# V2.net
KiCad netlist of a schematic drawn in EasyEDA
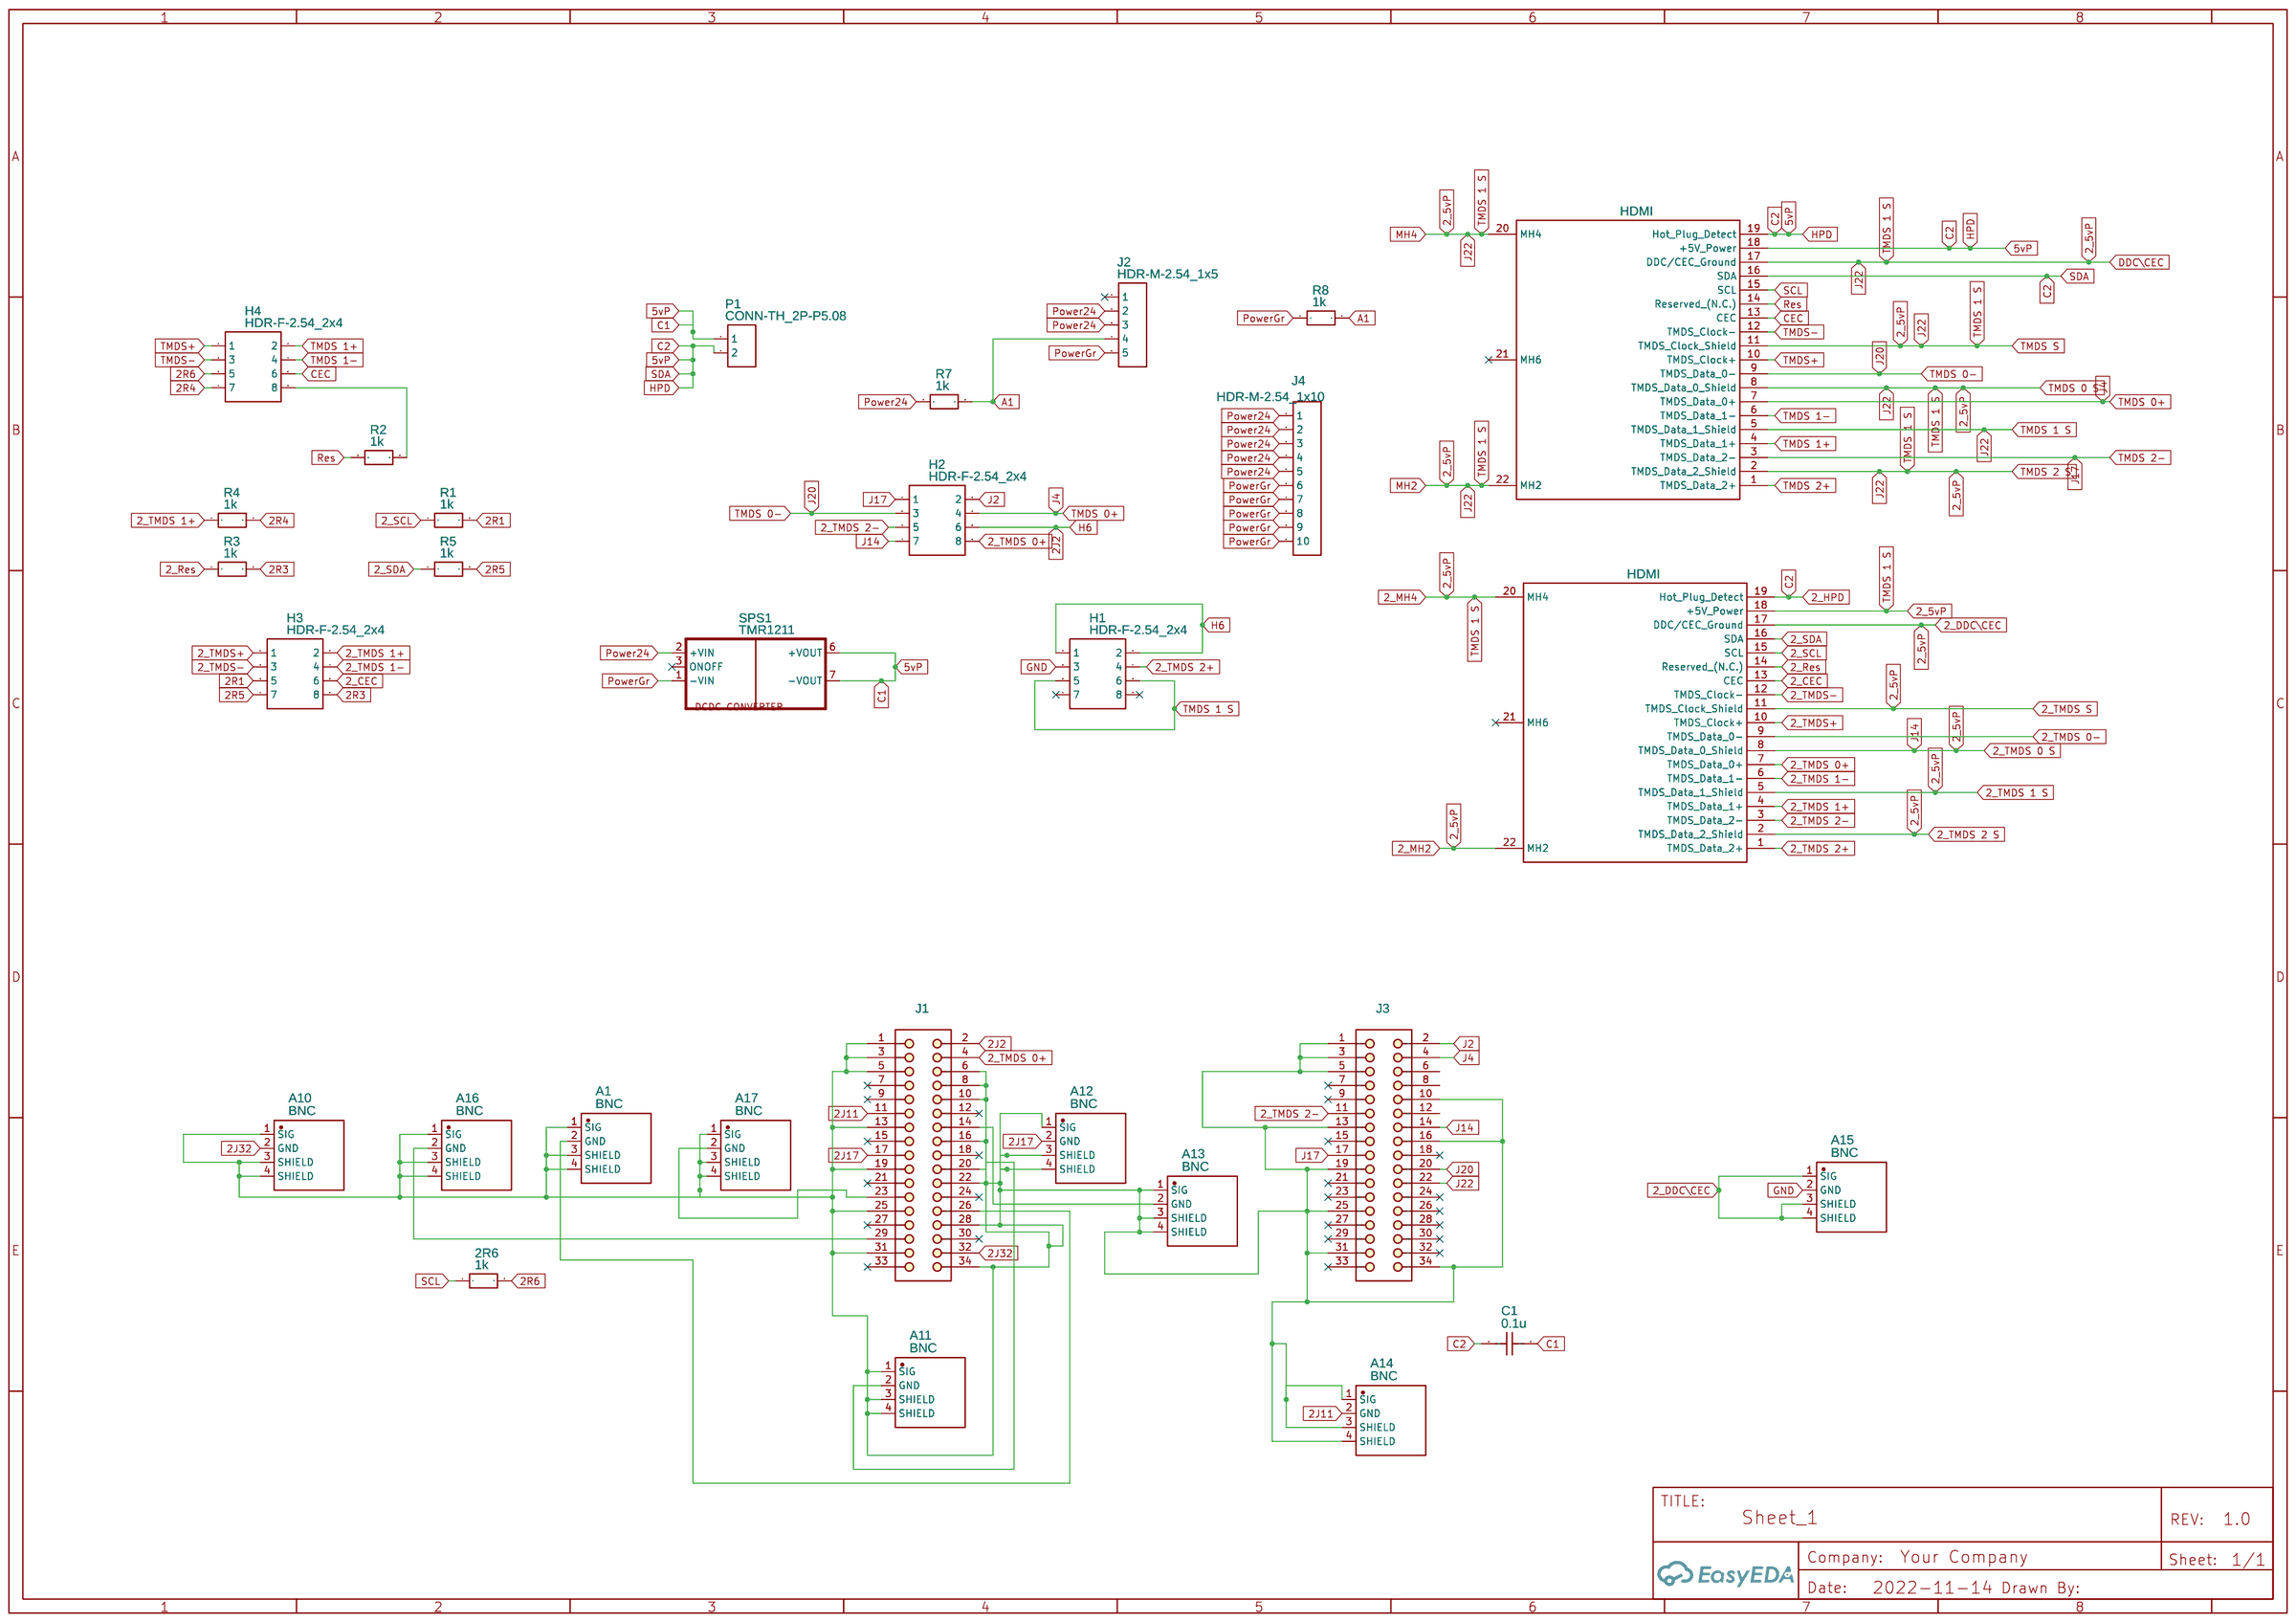
[diagram p0: schematic sheet]

(export (version "E")
  (design (tool "Eeschema 10.0.6"))
  (components
    (comp (ref "2R6") (value "1k") (libsource (lib "") (part "R_0603_EU_1")))
    (comp (ref "A1")
      (value "BNC")
      (fields
        (field (name "BOM_Manufacturer Part") "DOSIN-801-0039")
        (field (name "BOM_Supplier Part") "C709674")
      )
      (libsource (lib "") (part "DOSIN-801-0039"))
    )
    (comp (ref "A10")
      (value "BNC")
      (fields
        (field (name "BOM_Manufacturer Part") "DOSIN-801-0039")
        (field (name "BOM_Supplier Part") "C709674")
      )
      (libsource (lib "") (part "DOSIN-801-0039"))
    )
    (comp (ref "A11")
      (value "BNC")
      (fields
        (field (name "BOM_Manufacturer Part") "DOSIN-801-0039")
        (field (name "BOM_Supplier Part") "C709674")
      )
      (libsource (lib "") (part "DOSIN-801-0039"))
    )
    (comp (ref "A12")
      (value "BNC")
      (fields
        (field (name "BOM_Manufacturer Part") "DOSIN-801-0039")
        (field (name "BOM_Supplier Part") "C709674")
      )
      (libsource (lib "") (part "DOSIN-801-0039"))
    )
    (comp (ref "A13")
      (value "BNC")
      (fields
        (field (name "BOM_Manufacturer Part") "DOSIN-801-0039")
        (field (name "BOM_Supplier Part") "C709674")
      )
      (libsource (lib "") (part "DOSIN-801-0039"))
    )
    (comp (ref "A14")
      (value "BNC")
      (fields
        (field (name "BOM_Manufacturer Part") "DOSIN-801-0039")
        (field (name "BOM_Supplier Part") "C709674")
      )
      (libsource (lib "") (part "DOSIN-801-0039"))
    )
    (comp (ref "A15")
      (value "BNC")
      (fields
        (field (name "BOM_Manufacturer Part") "DOSIN-801-0039")
        (field (name "BOM_Supplier Part") "C709674")
      )
      (libsource (lib "") (part "DOSIN-801-0039"))
    )
    (comp (ref "A16")
      (value "BNC")
      (fields
        (field (name "BOM_Manufacturer Part") "DOSIN-801-0039")
        (field (name "BOM_Supplier Part") "C709674")
      )
      (libsource (lib "") (part "DOSIN-801-0039"))
    )
    (comp (ref "A17")
      (value "BNC")
      (fields
        (field (name "BOM_Manufacturer Part") "DOSIN-801-0039")
        (field (name "BOM_Supplier Part") "C709674")
      )
      (libsource (lib "") (part "DOSIN-801-0039"))
    )
    (comp (ref "C1") (value "0.1u") (libsource (lib "") (part "C_0603_US")))
    (comp (ref "H1")
      (value "HDR-F-2.54_2x4")
      (fields (field (name "BOM_Supplier Part") "C239344"))
      (libsource (lib "") (part "HDR-F-2.54_2x4"))
    )
    (comp (ref "H2")
      (value "HDR-F-2.54_2x4")
      (fields (field (name "BOM_Supplier Part") "C239344"))
      (libsource (lib "") (part "HDR-F-2.54_2x4"))
    )
    (comp (ref "H3")
      (value "HDR-F-2.54_2x4")
      (fields (field (name "BOM_Supplier Part") "C239344"))
      (libsource (lib "") (part "HDR-F-2.54_2x4"))
    )
    (comp (ref "H4")
      (value "HDR-F-2.54_2x4")
      (fields (field (name "BOM_Supplier Part") "C239344"))
      (libsource (lib "") (part "HDR-F-2.54_2x4"))
    )
    (comp (ref "J1") (value "09 18 134 9621") (libsource (lib "") (part "09 18 134 9621")))
    (comp (ref "J2")
      (value "HDR-M-2.54_1x5")
      (fields (field (name "BOM_Supplier Part") "C358687"))
      (libsource (lib "") (part "HDR-M-2.54_1x5"))
    )
    (comp (ref "J3") (value "09 18 134 9621") (libsource (lib "") (part "09 18 134 9621")))
    (comp (ref "J4")
      (value "HDR-M-2.54_1x10")
      (fields (field (name "BOM_Supplier Part") "C57369"))
      (libsource (lib "") (part "HDR-M-2.54_1x10"))
    )
    (comp (ref "P1") (value "CONN-TH_2P-P5.08") (libsource (lib "") (part "CONN-TH_2P-P5.08")))
    (comp (ref "R1") (value "1k") (libsource (lib "") (part "R_0603_EU")))
    (comp (ref "R2") (value "1k") (libsource (lib "") (part "R_0603_EU")))
    (comp (ref "R3") (value "1k") (libsource (lib "") (part "R_0603_EU")))
    (comp (ref "R4") (value "1k") (libsource (lib "") (part "R_0603_EU")))
    (comp (ref "R5") (value "1k") (libsource (lib "") (part "R_0603_EU")))
    (comp (ref "R7") (value "1k") (libsource (lib "") (part "R_0603_EU")))
    (comp (ref "R8") (value "1k") (libsource (lib "") (part "R_0603_EU")))
    (comp (ref "SPS1") (value "TMR1211") (libsource (lib "") (part "TMR1211")))
    (comp (ref "U1")
      (value "HDMI")
      (fields
        (field (name "BOM_Manufacturer Part") "HDMI-019L-S")
        (field (name "BOM_Supplier Part") "C3021272")
      )
      (libsource (lib "") (part "HDMI-019L-S"))
    )
    (comp (ref "U2")
      (value "HDMI")
      (fields
        (field (name "BOM_Manufacturer Part") "HDMI-019L-S")
        (field (name "BOM_Supplier Part") "C3021272")
      )
      (libsource (lib "") (part "HDMI-019L-S"))
    )
  )
  (nets
    (net (code "1") (name "2J2") (class "Default")
      (node (ref "H1") (pin "1") (pinfunction "1_1") (pintype "unspecified"))
      (node (ref "H1") (pin "2") (pinfunction "2_2") (pintype "unspecified"))
      (node (ref "H2") (pin "6") (pinfunction "6_6") (pintype "unspecified"))
      (node (ref "J1") (pin "2") (pinfunction "2_2") (pintype "unspecified"))
    )
    (net (code "2") (name "2J11") (class "Default")
      (node (ref "A14") (pin "2") (pinfunction "GND_2") (pintype "unspecified"))
      (node (ref "J1") (pin "11") (pinfunction "11_11") (pintype "unspecified"))
    )
    (net (code "3") (name "2J17") (class "Default")
      (node (ref "A12") (pin "2") (pinfunction "GND_2") (pintype "unspecified"))
      (node (ref "J1") (pin "17") (pinfunction "17_17") (pintype "unspecified"))
    )
    (net (code "4") (name "2J32") (class "Default")
      (node (ref "A10") (pin "2") (pinfunction "GND_2") (pintype "unspecified"))
      (node (ref "J1") (pin "32") (pinfunction "32_32") (pintype "unspecified"))
    )
    (net (code "5") (name "2R1") (class "Default")
      (node (ref "H3") (pin "5") (pinfunction "5_5") (pintype "unspecified"))
      (node (ref "R1") (pin "2") (pinfunction "2_2") (pintype "unspecified"))
    )
    (net (code "6") (name "2R3") (class "Default")
      (node (ref "H3") (pin "8") (pinfunction "8_8") (pintype "unspecified"))
      (node (ref "R3") (pin "2") (pinfunction "2_2") (pintype "unspecified"))
    )
    (net (code "7") (name "2R4") (class "Default")
      (node (ref "H4") (pin "7") (pinfunction "7_7") (pintype "unspecified"))
      (node (ref "R4") (pin "2") (pinfunction "2_2") (pintype "unspecified"))
    )
    (net (code "8") (name "2R5") (class "Default")
      (node (ref "H3") (pin "7") (pinfunction "7_7") (pintype "unspecified"))
      (node (ref "R5") (pin "2") (pinfunction "2_2") (pintype "unspecified"))
    )
    (net (code "9") (name "2R6") (class "Default")
      (node (ref "2R6") (pin "2") (pinfunction "2_2") (pintype "unspecified"))
      (node (ref "H4") (pin "5") (pinfunction "5_5") (pintype "unspecified"))
    )
    (net (code "10") (name "2_5vP") (class "Default")
      (node (ref "A15") (pin "1") (pinfunction "SIG_1") (pintype "unspecified"))
      (node (ref "A15") (pin "3") (pinfunction "SHIELD_3") (pintype "unspecified"))
      (node (ref "A15") (pin "4") (pinfunction "SHIELD_4") (pintype "unspecified"))
      (node (ref "H1") (pin "5") (pinfunction "5_5") (pintype "unspecified"))
      (node (ref "H1") (pin "6") (pinfunction "6_6") (pintype "unspecified"))
      (node (ref "H2") (pin "7") (pinfunction "7_7") (pintype "unspecified"))
      (node (ref "J3") (pin "14") (pinfunction "14_14") (pintype "unspecified"))
      (node (ref "J3") (pin "22") (pinfunction "22_22") (pintype "unspecified"))
      (node (ref "U1") (pin "11") (pinfunction "TMDS_Clock_Shield_11") (pintype "unspecified"))
      (node (ref "U1") (pin "17") (pinfunction "DDC/CEC_Ground_17") (pintype "unspecified"))
      (node (ref "U1") (pin "2") (pinfunction "TMDS_Data_2_Shield_2") (pintype "unspecified"))
      (node (ref "U1") (pin "20") (pinfunction "MH4_20") (pintype "unspecified"))
      (node (ref "U1") (pin "22") (pinfunction "MH2_22") (pintype "unspecified"))
      (node (ref "U1") (pin "5") (pinfunction "TMDS_Data_1_Shield_5") (pintype "unspecified"))
      (node (ref "U1") (pin "8") (pinfunction "TMDS_Data_0_Shield_8") (pintype "unspecified"))
      (node (ref "U2") (pin "11") (pinfunction "TMDS_Clock_Shield_11") (pintype "unspecified"))
      (node (ref "U2") (pin "17") (pinfunction "DDC/CEC_Ground_17") (pintype "unspecified"))
      (node (ref "U2") (pin "18") (pinfunction "+5V_Power_18") (pintype "unspecified"))
      (node (ref "U2") (pin "2") (pinfunction "TMDS_Data_2_Shield_2") (pintype "unspecified"))
      (node (ref "U2") (pin "20") (pinfunction "MH4_20") (pintype "unspecified"))
      (node (ref "U2") (pin "22") (pinfunction "MH2_22") (pintype "unspecified"))
      (node (ref "U2") (pin "5") (pinfunction "TMDS_Data_1_Shield_5") (pintype "unspecified"))
      (node (ref "U2") (pin "8") (pinfunction "TMDS_Data_0_Shield_8") (pintype "unspecified"))
    )
    (net (code "11") (name "2_CEC") (class "Default")
      (node (ref "H3") (pin "6") (pinfunction "6_6") (pintype "unspecified"))
      (node (ref "U2") (pin "13") (pinfunction "CEC_13") (pintype "unspecified"))
    )
    (net (code "12") (name "2_HPD") (class "Default")
      (node (ref "C1") (pin "1") (pinfunction "1_1") (pintype "unspecified"))
      (node (ref "C1") (pin "2") (pinfunction "2_2") (pintype "unspecified"))
      (node (ref "P1") (pin "1") (pinfunction "1_1") (pintype "unspecified"))
      (node (ref "P1") (pin "2") (pinfunction "2_2") (pintype "unspecified"))
      (node (ref "SPS1") (pin "6") (pinfunction "+VOUT_6") (pintype "unspecified"))
      (node (ref "SPS1") (pin "7") (pinfunction "-VOUT_7") (pintype "unspecified"))
      (node (ref "U1") (pin "16") (pinfunction "SDA_16") (pintype "unspecified"))
      (node (ref "U1") (pin "18") (pinfunction "+5V_Power_18") (pintype "unspecified"))
      (node (ref "U1") (pin "19") (pinfunction "Hot_Plug_Detect_19") (pintype "unspecified"))
      (node (ref "U2") (pin "19") (pinfunction "Hot_Plug_Detect_19") (pintype "unspecified"))
    )
    (net (code "13") (name "2_Res") (class "Default")
      (node (ref "R3") (pin "1") (pinfunction "1_1") (pintype "unspecified"))
      (node (ref "U2") (pin "14") (pinfunction "Reserved_(N.C.)_14") (pintype "unspecified"))
    )
    (net (code "14") (name "2_SCL") (class "Default")
      (node (ref "R1") (pin "1") (pinfunction "1_1") (pintype "unspecified"))
      (node (ref "U2") (pin "15") (pinfunction "SCL_15") (pintype "unspecified"))
    )
    (net (code "15") (name "2_SDA") (class "Default")
      (node (ref "R5") (pin "1") (pinfunction "1_1") (pintype "unspecified"))
      (node (ref "U2") (pin "16") (pinfunction "SDA_16") (pintype "unspecified"))
    )
    (net (code "16") (name "2_TMDS 0+") (class "Default")
      (node (ref "H2") (pin "8") (pinfunction "8_8") (pintype "unspecified"))
      (node (ref "J1") (pin "4") (pinfunction "4_4") (pintype "unspecified"))
      (node (ref "U2") (pin "7") (pinfunction "TMDS_Data_0+_7") (pintype "unspecified"))
    )
    (net (code "17") (name "2_TMDS 0-") (class "Default")
      (node (ref "U2") (pin "9") (pinfunction "TMDS_Data_0-_9") (pintype "unspecified"))
    )
    (net (code "18") (name "2_TMDS 1+") (class "Default")
      (node (ref "H3") (pin "2") (pinfunction "2_2") (pintype "unspecified"))
      (node (ref "R4") (pin "1") (pinfunction "1_1") (pintype "unspecified"))
      (node (ref "U2") (pin "4") (pinfunction "TMDS_Data_1+_4") (pintype "unspecified"))
    )
    (net (code "19") (name "2_TMDS 1-") (class "Default")
      (node (ref "H3") (pin "4") (pinfunction "4_4") (pintype "unspecified"))
      (node (ref "U2") (pin "6") (pinfunction "TMDS_Data_1-_6") (pintype "unspecified"))
    )
    (net (code "20") (name "2_TMDS 2+") (class "Default")
      (node (ref "H1") (pin "4") (pinfunction "4_4") (pintype "unspecified"))
      (node (ref "U2") (pin "1") (pinfunction "TMDS_Data_2+_1") (pintype "unspecified"))
    )
    (net (code "21") (name "2_TMDS 2-") (class "Default")
      (node (ref "H2") (pin "5") (pinfunction "5_5") (pintype "unspecified"))
      (node (ref "J3") (pin "11") (pinfunction "11_11") (pintype "unspecified"))
      (node (ref "U2") (pin "3") (pinfunction "TMDS_Data_2-_3") (pintype "unspecified"))
    )
    (net (code "22") (name "2_TMDS+") (class "Default")
      (node (ref "H3") (pin "1") (pinfunction "1_1") (pintype "unspecified"))
      (node (ref "U2") (pin "10") (pinfunction "TMDS_Clock+_10") (pintype "unspecified"))
    )
    (net (code "23") (name "2_TMDS-") (class "Default")
      (node (ref "H3") (pin "3") (pinfunction "3_3") (pintype "unspecified"))
      (node (ref "U2") (pin "12") (pinfunction "TMDS_Clock-_12") (pintype "unspecified"))
    )
    (net (code "24") (name "A1") (class "Default")
      (node (ref "J2") (pin "4") (pinfunction "4_4") (pintype "unspecified"))
      (node (ref "R7") (pin "2") (pinfunction "2_2") (pintype "unspecified"))
      (node (ref "R8") (pin "2") (pinfunction "2_2") (pintype "unspecified"))
    )
    (net (code "25") (name "CEC") (class "Default")
      (node (ref "H4") (pin "6") (pinfunction "6_6") (pintype "unspecified"))
      (node (ref "U1") (pin "13") (pinfunction "CEC_13") (pintype "unspecified"))
    )
    (net (code "26") (name "GND") (class "Default")
      (node (ref "A15") (pin "2") (pinfunction "GND_2") (pintype "unspecified"))
      (node (ref "H1") (pin "3") (pinfunction "3_3") (pintype "unspecified"))
    )
    (net (code "27") (name "J2") (class "Default")
      (node (ref "H2") (pin "2") (pinfunction "2_2") (pintype "unspecified"))
      (node (ref "J3") (pin "2") (pinfunction "2_2") (pintype "unspecified"))
    )
    (net (code "28") (name "J4") (class "Default")
      (node (ref "H2") (pin "4") (pinfunction "4_4") (pintype "unspecified"))
      (node (ref "J3") (pin "4") (pinfunction "4_4") (pintype "unspecified"))
      (node (ref "U1") (pin "7") (pinfunction "TMDS_Data_0+_7") (pintype "unspecified"))
    )
    (net (code "29") (name "J17") (class "Default")
      (node (ref "H2") (pin "1") (pinfunction "1_1") (pintype "unspecified"))
      (node (ref "J3") (pin "17") (pinfunction "17_17") (pintype "unspecified"))
      (node (ref "U1") (pin "3") (pinfunction "TMDS_Data_2-_3") (pintype "unspecified"))
    )
    (net (code "30") (name "J20") (class "Default")
      (node (ref "H2") (pin "3") (pinfunction "3_3") (pintype "unspecified"))
      (node (ref "J3") (pin "20") (pinfunction "20_20") (pintype "unspecified"))
      (node (ref "U1") (pin "9") (pinfunction "TMDS_Data_0-_9") (pintype "unspecified"))
    )
    (net (code "31") (name "Net-(A1-GND)") (class "Default")
      (node (ref "A1") (pin "2") (pinfunction "GND_2") (pintype "unspecified"))
      (node (ref "J1") (pin "26") (pinfunction "26_26") (pintype "unspecified"))
    )
    (net (code "32") (name "Net-(A1-SIG)") (class "Default")
      (node (ref "A1") (pin "1") (pinfunction "SIG_1") (pintype "unspecified"))
      (node (ref "A1") (pin "3") (pinfunction "SHIELD_3") (pintype "unspecified"))
      (node (ref "A1") (pin "4") (pinfunction "SHIELD_4") (pintype "unspecified"))
      (node (ref "A10") (pin "1") (pinfunction "SIG_1") (pintype "unspecified"))
      (node (ref "A10") (pin "3") (pinfunction "SHIELD_3") (pintype "unspecified"))
      (node (ref "A10") (pin "4") (pinfunction "SHIELD_4") (pintype "unspecified"))
      (node (ref "A11") (pin "1") (pinfunction "SIG_1") (pintype "unspecified"))
      (node (ref "A11") (pin "3") (pinfunction "SHIELD_3") (pintype "unspecified"))
      (node (ref "A11") (pin "4") (pinfunction "SHIELD_4") (pintype "unspecified"))
      (node (ref "A12") (pin "1") (pinfunction "SIG_1") (pintype "unspecified"))
      (node (ref "A12") (pin "3") (pinfunction "SHIELD_3") (pintype "unspecified"))
      (node (ref "A12") (pin "4") (pinfunction "SHIELD_4") (pintype "unspecified"))
      (node (ref "A13") (pin "1") (pinfunction "SIG_1") (pintype "unspecified"))
      (node (ref "A13") (pin "3") (pinfunction "SHIELD_3") (pintype "unspecified"))
      (node (ref "A13") (pin "4") (pinfunction "SHIELD_4") (pintype "unspecified"))
      (node (ref "A14") (pin "1") (pinfunction "SIG_1") (pintype "unspecified"))
      (node (ref "A14") (pin "3") (pinfunction "SHIELD_3") (pintype "unspecified"))
      (node (ref "A14") (pin "4") (pinfunction "SHIELD_4") (pintype "unspecified"))
      (node (ref "A16") (pin "1") (pinfunction "SIG_1") (pintype "unspecified"))
      (node (ref "A16") (pin "3") (pinfunction "SHIELD_3") (pintype "unspecified"))
      (node (ref "A16") (pin "4") (pinfunction "SHIELD_4") (pintype "unspecified"))
      (node (ref "A17") (pin "1") (pinfunction "SIG_1") (pintype "unspecified"))
      (node (ref "A17") (pin "3") (pinfunction "SHIELD_3") (pintype "unspecified"))
      (node (ref "A17") (pin "4") (pinfunction "SHIELD_4") (pintype "unspecified"))
      (node (ref "J1") (pin "1") (pinfunction "1_1") (pintype "unspecified"))
      (node (ref "J1") (pin "10") (pinfunction "10_10") (pintype "unspecified"))
      (node (ref "J1") (pin "13") (pinfunction "13_13") (pintype "unspecified"))
      (node (ref "J1") (pin "16") (pinfunction "16_16") (pintype "unspecified"))
      (node (ref "J1") (pin "19") (pinfunction "19_19") (pintype "unspecified"))
      (node (ref "J1") (pin "22") (pinfunction "22_22") (pintype "unspecified"))
      (node (ref "J1") (pin "25") (pinfunction "25_25") (pintype "unspecified"))
      (node (ref "J1") (pin "28") (pinfunction "28_28") (pintype "unspecified"))
      (node (ref "J1") (pin "3") (pinfunction "3_3") (pintype "unspecified"))
      (node (ref "J1") (pin "31") (pinfunction "31_31") (pintype "unspecified"))
      (node (ref "J1") (pin "34") (pinfunction "34_34") (pintype "unspecified"))
      (node (ref "J1") (pin "5") (pinfunction "5_5") (pintype "unspecified"))
      (node (ref "J1") (pin "6") (pinfunction "6_6") (pintype "unspecified"))
      (node (ref "J1") (pin "8") (pinfunction "8_8") (pintype "unspecified"))
      (node (ref "J3") (pin "1") (pinfunction "1_1") (pintype "unspecified"))
      (node (ref "J3") (pin "10") (pinfunction "10_10") (pintype "unspecified"))
      (node (ref "J3") (pin "13") (pinfunction "13_13") (pintype "unspecified"))
      (node (ref "J3") (pin "16") (pinfunction "16_16") (pintype "unspecified"))
      (node (ref "J3") (pin "19") (pinfunction "19_19") (pintype "unspecified"))
      (node (ref "J3") (pin "25") (pinfunction "25_25") (pintype "unspecified"))
      (node (ref "J3") (pin "3") (pinfunction "3_3") (pintype "unspecified"))
      (node (ref "J3") (pin "31") (pinfunction "31_31") (pintype "unspecified"))
      (node (ref "J3") (pin "34") (pinfunction "34_34") (pintype "unspecified"))
      (node (ref "J3") (pin "5") (pinfunction "5_5") (pintype "unspecified"))
    )
    (net (code "33") (name "Net-(A11-GND)") (class "Default")
      (node (ref "A11") (pin "2") (pinfunction "GND_2") (pintype "unspecified"))
      (node (ref "J1") (pin "20") (pinfunction "20_20") (pintype "unspecified"))
    )
    (net (code "34") (name "Net-(A13-GND)") (class "Default")
      (node (ref "A13") (pin "2") (pinfunction "GND_2") (pintype "unspecified"))
      (node (ref "J1") (pin "14") (pinfunction "14_14") (pintype "unspecified"))
    )
    (net (code "35") (name "Net-(A16-GND)") (class "Default")
      (node (ref "A16") (pin "2") (pinfunction "GND_2") (pintype "unspecified"))
      (node (ref "J1") (pin "29") (pinfunction "29_29") (pintype "unspecified"))
    )
    (net (code "36") (name "Net-(A17-GND)") (class "Default")
      (node (ref "A17") (pin "2") (pinfunction "GND_2") (pintype "unspecified"))
      (node (ref "J1") (pin "23") (pinfunction "23_23") (pintype "unspecified"))
    )
    (net (code "37") (name "Net-(H4-Pad8)") (class "Default")
      (node (ref "H4") (pin "8") (pinfunction "8_8") (pintype "unspecified"))
      (node (ref "R2") (pin "2") (pinfunction "2_2") (pintype "unspecified"))
    )
    (net (code "38") (name "Power24") (class "Default")
      (node (ref "J2") (pin "2") (pinfunction "2_2") (pintype "unspecified"))
      (node (ref "J2") (pin "3") (pinfunction "3_3") (pintype "unspecified"))
      (node (ref "J4") (pin "1") (pinfunction "1_1") (pintype "unspecified"))
      (node (ref "J4") (pin "2") (pinfunction "2_2") (pintype "unspecified"))
      (node (ref "J4") (pin "3") (pinfunction "3_3") (pintype "unspecified"))
      (node (ref "J4") (pin "4") (pinfunction "4_4") (pintype "unspecified"))
      (node (ref "J4") (pin "5") (pinfunction "5_5") (pintype "unspecified"))
      (node (ref "R7") (pin "1") (pinfunction "1_1") (pintype "unspecified"))
      (node (ref "SPS1") (pin "2") (pinfunction "+VIN_2") (pintype "passive"))
    )
    (net (code "39") (name "PowerGr") (class "Default")
      (node (ref "J2") (pin "5") (pinfunction "5_5") (pintype "unspecified"))
      (node (ref "J4") (pin "10") (pinfunction "10_10") (pintype "unspecified"))
      (node (ref "J4") (pin "6") (pinfunction "6_6") (pintype "unspecified"))
      (node (ref "J4") (pin "7") (pinfunction "7_7") (pintype "unspecified"))
      (node (ref "J4") (pin "8") (pinfunction "8_8") (pintype "unspecified"))
      (node (ref "J4") (pin "9") (pinfunction "9_9") (pintype "unspecified"))
      (node (ref "R8") (pin "1") (pinfunction "1_1") (pintype "unspecified"))
      (node (ref "SPS1") (pin "1") (pinfunction "-VIN_1") (pintype "passive"))
    )
    (net (code "40") (name "Res") (class "Default")
      (node (ref "R2") (pin "1") (pinfunction "1_1") (pintype "unspecified"))
      (node (ref "U1") (pin "14") (pinfunction "Reserved_(N.C.)_14") (pintype "unspecified"))
    )
    (net (code "41") (name "SCL") (class "Default")
      (node (ref "2R6") (pin "1") (pinfunction "1_1") (pintype "unspecified"))
      (node (ref "U1") (pin "15") (pinfunction "SCL_15") (pintype "unspecified"))
    )
    (net (code "42") (name "TMDS 1+") (class "Default")
      (node (ref "H4") (pin "2") (pinfunction "2_2") (pintype "unspecified"))
      (node (ref "U1") (pin "4") (pinfunction "TMDS_Data_1+_4") (pintype "unspecified"))
    )
    (net (code "43") (name "TMDS 1-") (class "Default")
      (node (ref "H4") (pin "4") (pinfunction "4_4") (pintype "unspecified"))
      (node (ref "U1") (pin "6") (pinfunction "TMDS_Data_1-_6") (pintype "unspecified"))
    )
    (net (code "44") (name "TMDS 2+") (class "Default")
      (node (ref "U1") (pin "1") (pinfunction "TMDS_Data_2+_1") (pintype "unspecified"))
    )
    (net (code "45") (name "TMDS+") (class "Default")
      (node (ref "H4") (pin "1") (pinfunction "1_1") (pintype "unspecified"))
      (node (ref "U1") (pin "10") (pinfunction "TMDS_Clock+_10") (pintype "unspecified"))
    )
    (net (code "46") (name "TMDS-") (class "Default")
      (node (ref "H4") (pin "3") (pinfunction "3_3") (pintype "unspecified"))
      (node (ref "U1") (pin "12") (pinfunction "TMDS_Clock-_12") (pintype "unspecified"))
    )
    (net (code "47") (name "unconnected-(H1-Pad7)") (class "Default")
      (node (ref "H1") (pin "7") (pinfunction "7_7") (pintype "unspecified+no_connect"))
    )
    (net (code "48") (name "unconnected-(H1-Pad8)") (class "Default")
      (node (ref "H1") (pin "8") (pinfunction "8_8") (pintype "unspecified+no_connect"))
    )
    (net (code "49") (name "unconnected-(J1-Pad7)") (class "Default")
      (node (ref "J1") (pin "7") (pinfunction "7_7") (pintype "unspecified+no_connect"))
    )
    (net (code "50") (name "unconnected-(J1-Pad9)") (class "Default")
      (node (ref "J1") (pin "9") (pinfunction "9_9") (pintype "unspecified+no_connect"))
    )
    (net (code "51") (name "unconnected-(J1-Pad12)") (class "Default")
      (node (ref "J1") (pin "12") (pinfunction "12_12") (pintype "unspecified+no_connect"))
    )
    (net (code "52") (name "unconnected-(J1-Pad15)") (class "Default")
      (node (ref "J1") (pin "15") (pinfunction "15_15") (pintype "unspecified+no_connect"))
    )
    (net (code "53") (name "unconnected-(J1-Pad18)") (class "Default")
      (node (ref "J1") (pin "18") (pinfunction "18_18") (pintype "unspecified+no_connect"))
    )
    (net (code "54") (name "unconnected-(J1-Pad21)") (class "Default")
      (node (ref "J1") (pin "21") (pinfunction "21_21") (pintype "unspecified+no_connect"))
    )
    (net (code "55") (name "unconnected-(J1-Pad24)") (class "Default")
      (node (ref "J1") (pin "24") (pinfunction "24_24") (pintype "unspecified+no_connect"))
    )
    (net (code "56") (name "unconnected-(J1-Pad27)") (class "Default")
      (node (ref "J1") (pin "27") (pinfunction "27_27") (pintype "unspecified+no_connect"))
    )
    (net (code "57") (name "unconnected-(J1-Pad30)") (class "Default")
      (node (ref "J1") (pin "30") (pinfunction "30_30") (pintype "unspecified+no_connect"))
    )
    (net (code "58") (name "unconnected-(J1-Pad33)") (class "Default")
      (node (ref "J1") (pin "33") (pinfunction "33_33") (pintype "unspecified+no_connect"))
    )
    (net (code "59") (name "unconnected-(J2-Pad1)") (class "Default")
      (node (ref "J2") (pin "1") (pinfunction "1_1") (pintype "unspecified+no_connect"))
    )
    (net (code "60") (name "unconnected-(J3-Pad6)") (class "Default")
      (node (ref "J3") (pin "6") (pinfunction "6_6") (pintype "unspecified"))
    )
    (net (code "61") (name "unconnected-(J3-Pad7)") (class "Default")
      (node (ref "J3") (pin "7") (pinfunction "7_7") (pintype "unspecified+no_connect"))
    )
    (net (code "62") (name "unconnected-(J3-Pad8)") (class "Default")
      (node (ref "J3") (pin "8") (pinfunction "8_8") (pintype "unspecified"))
    )
    (net (code "63") (name "unconnected-(J3-Pad9)") (class "Default")
      (node (ref "J3") (pin "9") (pinfunction "9_9") (pintype "unspecified+no_connect"))
    )
    (net (code "64") (name "unconnected-(J3-Pad12)") (class "Default")
      (node (ref "J3") (pin "12") (pinfunction "12_12") (pintype "unspecified"))
    )
    (net (code "65") (name "unconnected-(J3-Pad15)") (class "Default")
      (node (ref "J3") (pin "15") (pinfunction "15_15") (pintype "unspecified+no_connect"))
    )
    (net (code "66") (name "unconnected-(J3-Pad18)") (class "Default")
      (node (ref "J3") (pin "18") (pinfunction "18_18") (pintype "unspecified+no_connect"))
    )
    (net (code "67") (name "unconnected-(J3-Pad21)") (class "Default")
      (node (ref "J3") (pin "21") (pinfunction "21_21") (pintype "unspecified+no_connect"))
    )
    (net (code "68") (name "unconnected-(J3-Pad23)") (class "Default")
      (node (ref "J3") (pin "23") (pinfunction "23_23") (pintype "unspecified+no_connect"))
    )
    (net (code "69") (name "unconnected-(J3-Pad24)") (class "Default")
      (node (ref "J3") (pin "24") (pinfunction "24_24") (pintype "unspecified+no_connect"))
    )
    (net (code "70") (name "unconnected-(J3-Pad26)") (class "Default")
      (node (ref "J3") (pin "26") (pinfunction "26_26") (pintype "unspecified+no_connect"))
    )
    (net (code "71") (name "unconnected-(J3-Pad27)") (class "Default")
      (node (ref "J3") (pin "27") (pinfunction "27_27") (pintype "unspecified+no_connect"))
    )
    (net (code "72") (name "unconnected-(J3-Pad28)") (class "Default")
      (node (ref "J3") (pin "28") (pinfunction "28_28") (pintype "unspecified+no_connect"))
    )
    (net (code "73") (name "unconnected-(J3-Pad29)") (class "Default")
      (node (ref "J3") (pin "29") (pinfunction "29_29") (pintype "unspecified+no_connect"))
    )
    (net (code "74") (name "unconnected-(J3-Pad30)") (class "Default")
      (node (ref "J3") (pin "30") (pinfunction "30_30") (pintype "unspecified+no_connect"))
    )
    (net (code "75") (name "unconnected-(J3-Pad32)") (class "Default")
      (node (ref "J3") (pin "32") (pinfunction "32_32") (pintype "unspecified+no_connect"))
    )
    (net (code "76") (name "unconnected-(J3-Pad33)") (class "Default")
      (node (ref "J3") (pin "33") (pinfunction "33_33") (pintype "unspecified+no_connect"))
    )
    (net (code "77") (name "unconnected-(SPS1-ONOFF-Pad3)") (class "Default")
      (node (ref "SPS1") (pin "3") (pinfunction "ONOFF_3") (pintype "unspecified+no_connect"))
    )
    (net (code "78") (name "unconnected-(U1-MH6-Pad21)") (class "Default")
      (node (ref "U1") (pin "21") (pinfunction "MH6_21") (pintype "unspecified+no_connect"))
    )
    (net (code "79") (name "unconnected-(U2-MH6-Pad21)") (class "Default")
      (node (ref "U2") (pin "21") (pinfunction "MH6_21") (pintype "unspecified+no_connect"))
    )
  )
)
